# tut-2.net
KiCad netlist of a schematic drawn in EAGLE
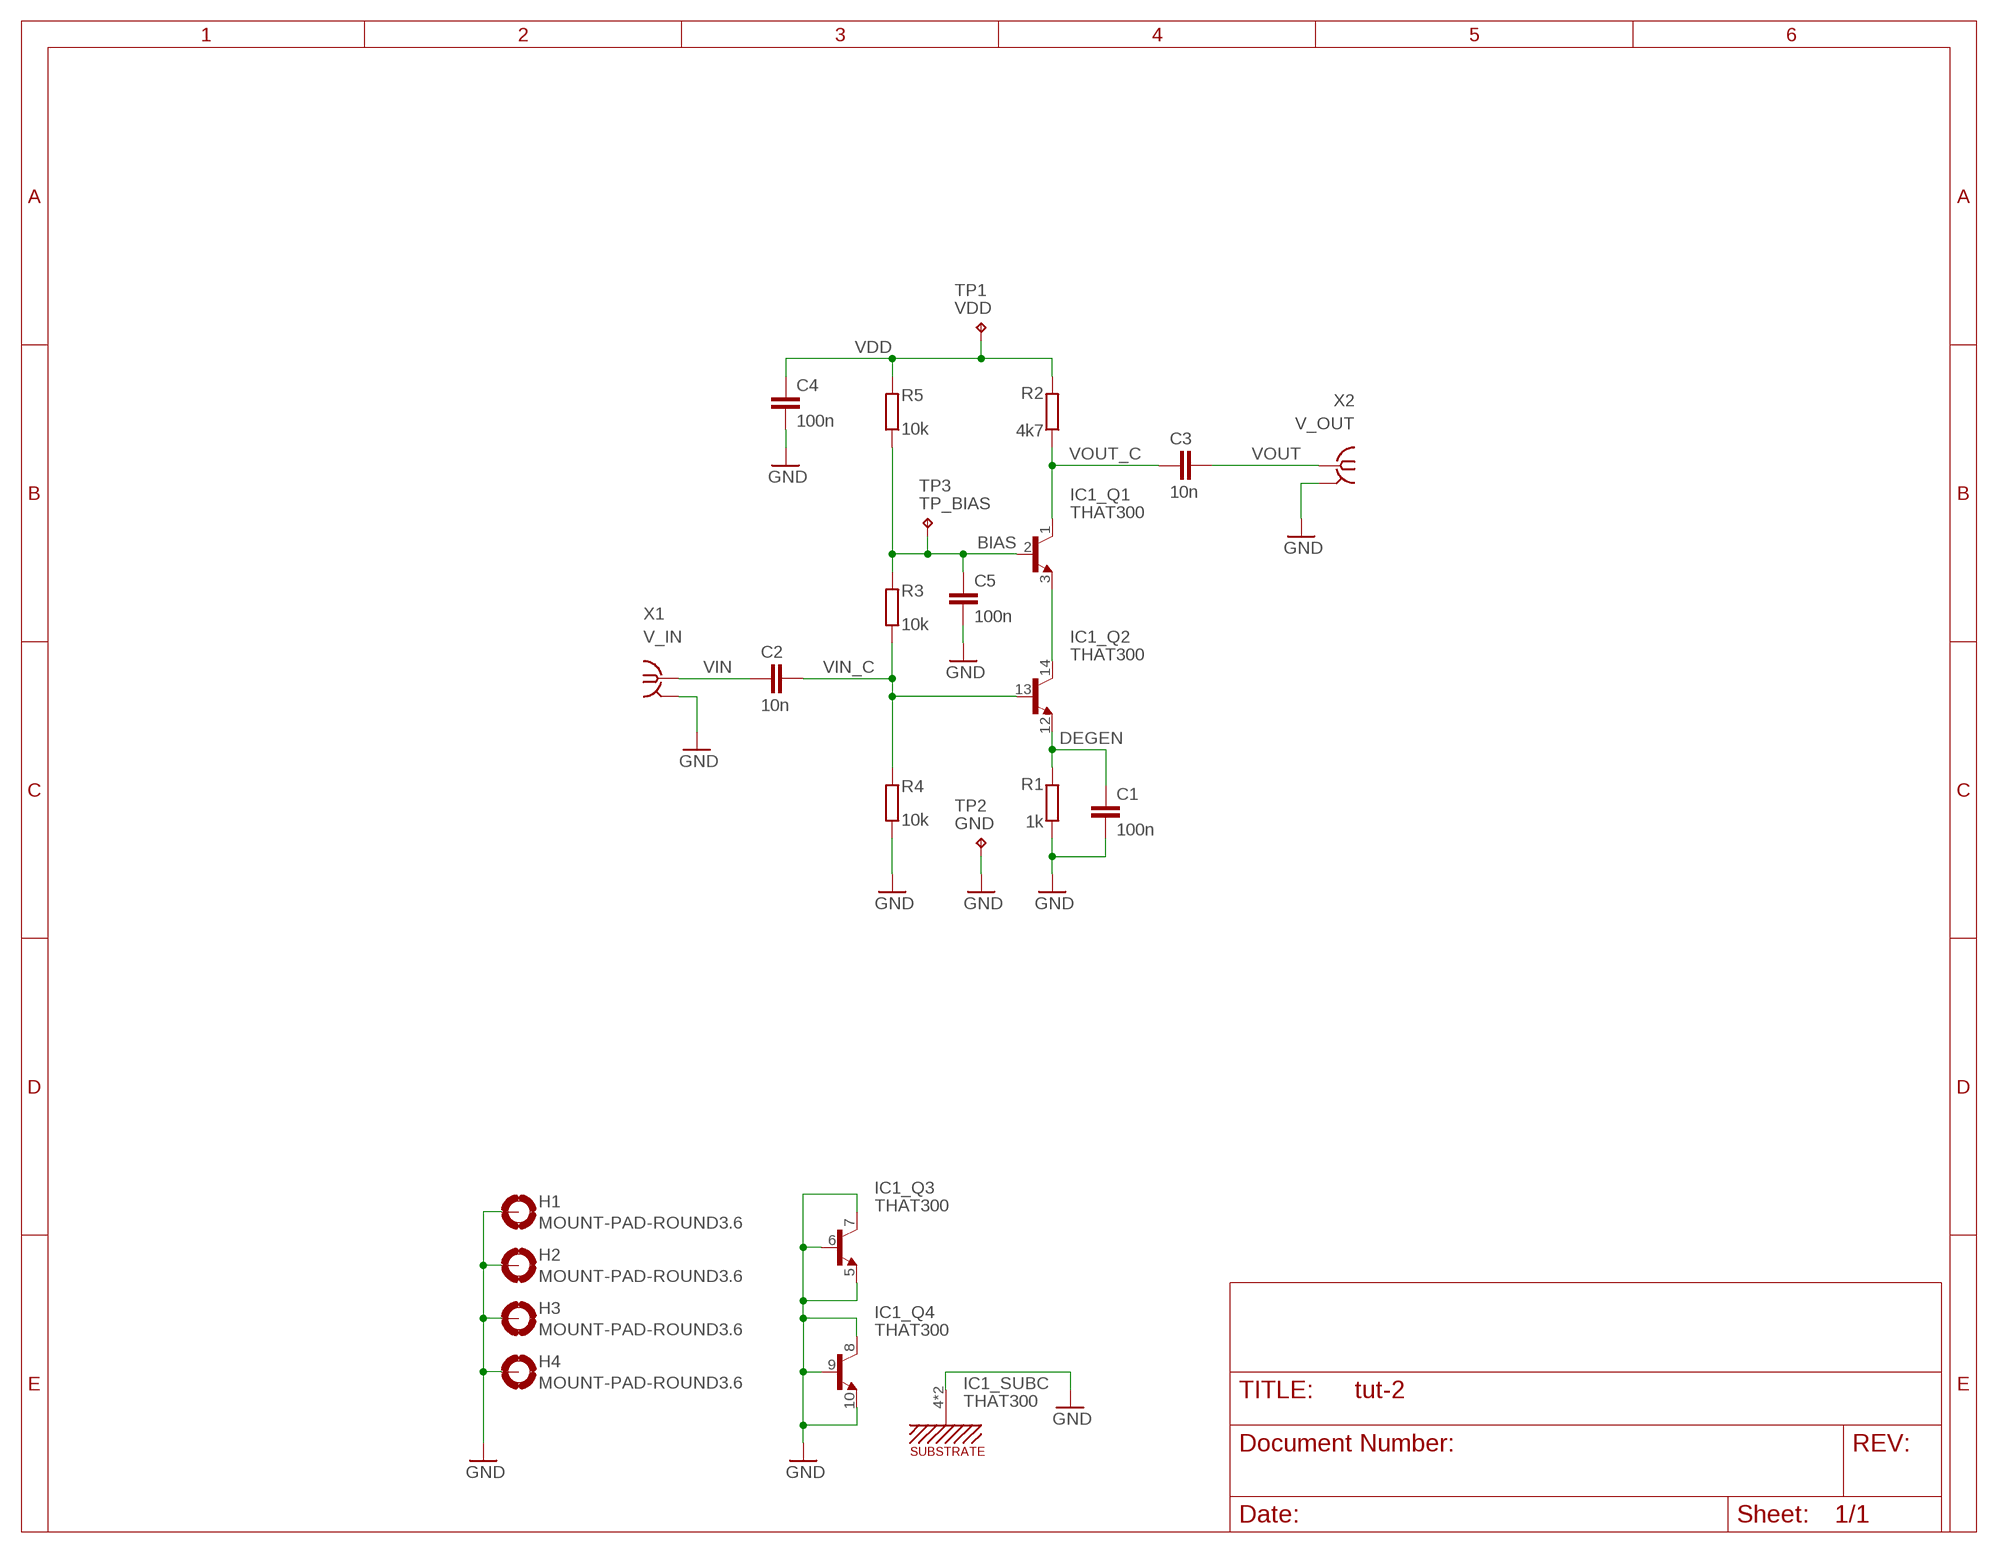
[diagram p0: schematic, sheet 1]

(export (version "E")
  (design (tool "Eeschema 10.0.6"))
  (components
    (comp (ref "C1")
      (value "100n")
      (footprint "eagle-import:C050-025X075")
      (libsource (lib "eagle-import") (part "C-EU050-025X075"))
    )
    (comp (ref "C2")
      (value "10n")
      (footprint "eagle-import:C050-025X075")
      (libsource (lib "eagle-import") (part "C-EU050-025X075"))
    )
    (comp (ref "C3")
      (value "10n")
      (footprint "eagle-import:C050-025X075")
      (libsource (lib "eagle-import") (part "C-EU050-025X075"))
    )
    (comp (ref "C4")
      (value "100n")
      (footprint "eagle-import:C050-025X075")
      (libsource (lib "eagle-import") (part "C-EU050-025X075"))
    )
    (comp (ref "C5")
      (value "100n")
      (footprint "eagle-import:C050-025X075")
      (libsource (lib "eagle-import") (part "C-EU050-025X075"))
    )
    (comp (ref "H1")
      (value "MOUNT-PAD-ROUND3.6")
      (footprint "eagle-import:3,6-PAD")
      (libsource (lib "eagle-import") (part "MOUNT-PAD-ROUND3.6"))
    )
    (comp (ref "H2")
      (value "MOUNT-PAD-ROUND3.6")
      (footprint "eagle-import:3,6-PAD")
      (libsource (lib "eagle-import") (part "MOUNT-PAD-ROUND3.6"))
    )
    (comp (ref "H3")
      (value "MOUNT-PAD-ROUND3.6")
      (footprint "eagle-import:3,6-PAD")
      (libsource (lib "eagle-import") (part "MOUNT-PAD-ROUND3.6"))
    )
    (comp (ref "H4")
      (value "MOUNT-PAD-ROUND3.6")
      (footprint "eagle-import:3,6-PAD")
      (libsource (lib "eagle-import") (part "MOUNT-PAD-ROUND3.6"))
    )
    (comp (ref "IC1")
      (value "THAT300")
      (footprint "eagle-import:DIL14")
      (libsource (lib "eagle-import") (part "THAT300"))
    )
    (comp (ref "R1")
      (value "1k")
      (footprint "eagle-import:0207_7")
      (libsource (lib "eagle-import") (part "R-EU_0207/7"))
    )
    (comp (ref "R2")
      (value "4k7")
      (footprint "eagle-import:0207_7")
      (libsource (lib "eagle-import") (part "R-EU_0207/7"))
    )
    (comp (ref "R3")
      (value "10k")
      (footprint "eagle-import:0207_7")
      (libsource (lib "eagle-import") (part "R-EU_0207/7"))
    )
    (comp (ref "R4")
      (value "10k")
      (footprint "eagle-import:0207_7")
      (libsource (lib "eagle-import") (part "R-EU_0207/7"))
    )
    (comp (ref "R5")
      (value "10k")
      (footprint "eagle-import:0207_7")
      (libsource (lib "eagle-import") (part "R-EU_0207/7"))
    )
    (comp (ref "TP1")
      (value "VDD")
      (footprint "eagle-import:KEYSTONE_5000_MINIATURE")
      (libsource (lib "eagle-import") (part "TESTPOINT"))
    )
    (comp (ref "TP2")
      (value "GND")
      (footprint "eagle-import:KEYSTONE_5000_MINIATURE")
      (libsource (lib "eagle-import") (part "TESTPOINT"))
    )
    (comp (ref "TP3")
      (value "TP_BIAS")
      (footprint "eagle-import:KEYSTONE_5000_MINIATURE")
      (libsource (lib "eagle-import") (part "TESTPOINT"))
    )
    (comp (ref "X1")
      (value "V_IN")
      (footprint "eagle-import:BU-SMA-H")
      (libsource (lib "eagle-import") (part "BU-SMA-H"))
    )
    (comp (ref "X2")
      (value "V_OUT")
      (footprint "eagle-import:BU-SMA-H")
      (libsource (lib "eagle-import") (part "BU-SMA-H"))
    )
  )
  (nets
    (net (code "1") (name "/BIAS") (class "Default")
      (node (ref "C5") (pin "1") (pinfunction "1_1") (pintype "passive"))
      (node (ref "IC1") (pin "2") (pinfunction "B_2") (pintype "passive"))
      (node (ref "R3") (pin "2") (pinfunction "2_2") (pintype "passive"))
      (node (ref "R5") (pin "1") (pinfunction "1_1") (pintype "passive"))
      (node (ref "TP3") (pin "P$1") (pinfunction "P$1_P$1") (pintype "bidirectional"))
    )
    (net (code "2") (name "/DEGEN") (class "Default")
      (node (ref "C1") (pin "1") (pinfunction "1_1") (pintype "passive"))
      (node (ref "IC1") (pin "12") (pinfunction "E_12") (pintype "passive"))
      (node (ref "R1") (pin "2") (pinfunction "2_2") (pintype "passive"))
    )
    (net (code "3") (name "/VDD") (class "Default")
      (node (ref "C4") (pin "1") (pinfunction "1_1") (pintype "passive"))
      (node (ref "R2") (pin "2") (pinfunction "2_2") (pintype "passive"))
      (node (ref "R5") (pin "2") (pinfunction "2_2") (pintype "passive"))
      (node (ref "TP1") (pin "P$1") (pinfunction "P$1_P$1") (pintype "bidirectional"))
    )
    (net (code "4") (name "/VIN") (class "Default")
      (node (ref "C2") (pin "1") (pinfunction "1_1") (pintype "passive"))
      (node (ref "X1") (pin "1") (pinfunction "1_1") (pintype "passive"))
    )
    (net (code "5") (name "/VIN_C") (class "Default")
      (node (ref "C2") (pin "2") (pinfunction "2_2") (pintype "passive"))
      (node (ref "IC1") (pin "13") (pinfunction "B_13") (pintype "passive"))
      (node (ref "R3") (pin "1") (pinfunction "1_1") (pintype "passive"))
      (node (ref "R4") (pin "2") (pinfunction "2_2") (pintype "passive"))
    )
    (net (code "6") (name "/VOUT") (class "Default")
      (node (ref "C3") (pin "2") (pinfunction "2_2") (pintype "passive"))
      (node (ref "X2") (pin "1") (pinfunction "1_1") (pintype "passive"))
    )
    (net (code "7") (name "/VOUT_C") (class "Default")
      (node (ref "C3") (pin "1") (pinfunction "1_1") (pintype "passive"))
      (node (ref "IC1") (pin "1") (pinfunction "C_1") (pintype "passive"))
      (node (ref "R2") (pin "1") (pinfunction "1_1") (pintype "passive"))
    )
    (net (code "8") (name "GND") (class "Default")
      (node (ref "C1") (pin "2") (pinfunction "2_2") (pintype "passive"))
      (node (ref "C4") (pin "2") (pinfunction "2_2") (pintype "passive"))
      (node (ref "C5") (pin "2") (pinfunction "2_2") (pintype "passive"))
      (node (ref "H1") (pin "B3,6") (pinfunction "MOUNT_B3,6") (pintype "passive"))
      (node (ref "H2") (pin "B3,6") (pinfunction "MOUNT_B3,6") (pintype "passive"))
      (node (ref "H3") (pin "B3,6") (pinfunction "MOUNT_B3,6") (pintype "passive"))
      (node (ref "H4") (pin "B3,6") (pinfunction "MOUNT_B3,6") (pintype "passive"))
      (node (ref "IC1") (pin "10") (pinfunction "E_10") (pintype "passive"))
      (node (ref "IC1") (pin "11") (pinfunction "SUBC_11") (pintype "bidirectional"))
      (node (ref "IC1") (pin "4") (pinfunction "SUBC_4") (pintype "bidirectional"))
      (node (ref "IC1") (pin "5") (pinfunction "E_5") (pintype "passive"))
      (node (ref "IC1") (pin "6") (pinfunction "B_6") (pintype "passive"))
      (node (ref "IC1") (pin "7") (pinfunction "C_7") (pintype "passive"))
      (node (ref "IC1") (pin "8") (pinfunction "C_8") (pintype "passive"))
      (node (ref "IC1") (pin "9") (pinfunction "B_9") (pintype "passive"))
      (node (ref "R1") (pin "1") (pinfunction "1_1") (pintype "passive"))
      (node (ref "R4") (pin "1") (pinfunction "1_1") (pintype "passive"))
      (node (ref "TP2") (pin "P$1") (pinfunction "P$1_P$1") (pintype "bidirectional"))
      (node (ref "X1") (pin "2") (pinfunction "2_2") (pintype "passive"))
      (node (ref "X1") (pin "3") (pinfunction "2_3") (pintype "passive"))
      (node (ref "X1") (pin "4") (pinfunction "2_4") (pintype "passive"))
      (node (ref "X1") (pin "5") (pinfunction "2_5") (pintype "passive"))
      (node (ref "X2") (pin "2") (pinfunction "2_2") (pintype "passive"))
      (node (ref "X2") (pin "3") (pinfunction "2_3") (pintype "passive"))
      (node (ref "X2") (pin "4") (pinfunction "2_4") (pintype "passive"))
      (node (ref "X2") (pin "5") (pinfunction "2_5") (pintype "passive"))
    )
    (net (code "9") (name "Net-(IC1A-E)") (class "Default")
      (node (ref "IC1") (pin "14") (pinfunction "C_14") (pintype "passive"))
      (node (ref "IC1") (pin "3") (pinfunction "E_3") (pintype "passive"))
    )
  )
)
